# Radio.net
KiCad netlist of a schematic drawn in Altium Designer
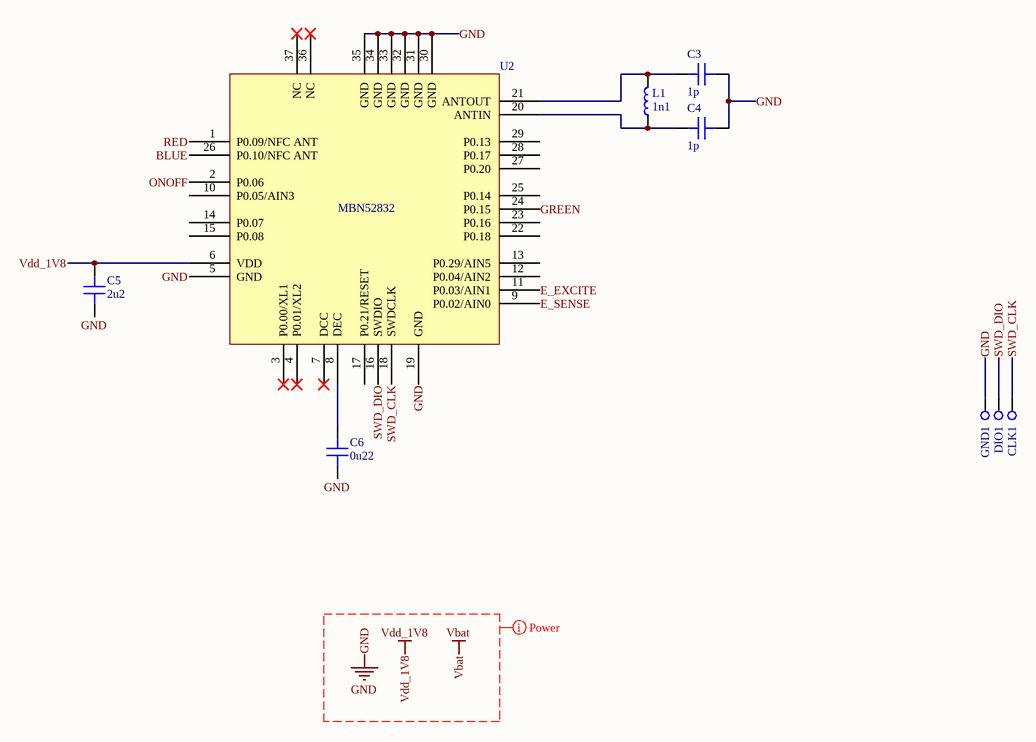
[diagram p0: Radio.SchDoc]

(export (version "E")
  (design (tool "Eeschema 10.0.6"))
  (components
    (comp (ref "C3")
      (value "1p")
      (footprint "CAP 0201/0603")
      (description "CAP CER 0201 1pF 50V ±0.1pF C0G")
      (fields (field (name "PART NUMBER") "GRM0335C1H1R0BA01D") (field (name "MANUFACTURER") "Murata"))
      (libsource (lib "ekuore-library") (part "Capacitor"))
    )
    (comp (ref "C4")
      (value "1p")
      (footprint "CAP 0201/0603")
      (description "CAP CER 0201 1pF 50V ±0.1pF C0G")
      (fields (field (name "PART NUMBER") "GRM0335C1H1R0BA01D") (field (name "MANUFACTURER") "Murata"))
      (libsource (lib "ekuore-library") (part "Capacitor"))
    )
    (comp (ref "C5")
      (value "2u2")
      (footprint "CAP 0402/1005")
      (description "CAP CER 0402 2.2uF 16V 10% X5R")
      (fields (field (name "PART NUMBER") "GRM155R61C225KE11D") (field (name "MANUFACTURER") "Murata"))
      (libsource (lib "ekuore-library") (part "Capacitor"))
    )
    (comp (ref "C6")
      (value "0u22")
      (footprint "CAP 0201/0603")
      (description "CAP CER 0201 0.22uF 10V 10% X5R")
      (fields (field (name "PART NUMBER") "GRM033R61A224KE90D") (field (name "MANUFACTURER") "Murata"))
      (libsource (lib "ekuore-library") (part "Capacitor"))
    )
    (comp (ref "CLK1")
      (value "Test Point")
      (footprint "TP SMD 1MM")
      (description "TP 1mm round pad")
      (fields (field (name "PART NUMBER") "TPSMD1"))
      (libsource (lib "ekuore-library") (part "Test Point"))
    )
    (comp (ref "DIO1")
      (value "Test Point")
      (footprint "TP SMD 1MM")
      (description "TP 1mm round pad")
      (fields (field (name "PART NUMBER") "TPSMD1"))
      (libsource (lib "ekuore-library") (part "Test Point"))
    )
    (comp (ref "GND1")
      (value "Test Point")
      (footprint "TP SMD 1MM")
      (description "TP 1mm round pad")
      (fields (field (name "PART NUMBER") "TPSMD1"))
      (libsource (lib "ekuore-library") (part "Test Point"))
    )
    (comp (ref "L1")
      (value "1n1")
      (footprint "FER 0402/1005")
      (description "IND 0201 1.1nH +-0.1nH 0.75A 0.1R")
      (fields (field (name "PART NUMBER") "LQP03TN1N1B02D_mod") (field (name "MANUFACTURER") "Murata"))
      (libsource (lib "ekuore-library") (part "Inductor"))
    )
    (comp (ref "U2")
      (value "MBN52832")
      (footprint "Murata MBN52832")
      (description "Bluetooth v5.0 (BLE) SMART SOC IoT/NFC 1Mbps 3.3V")
      (fields (field (name "PART NUMBER") "WSM-BL241-ADA-008") (field (name "MANUFACTURER") "Murata"))
      (libsource (lib "ekuore-library") (part "Murata MBN52832"))
    )
  )
  (nets
    (net (code "1") (name "/BLUE") (class "Default")
      (node (ref "U2") (pin "26") (pinfunction "P0.10/NFC_ANT_26") (pintype "passive"))
    )
    (net (code "2") (name "/E_EXCITE") (class "Default")
      (node (ref "U2") (pin "11") (pinfunction "P0.03/AIN1_11") (pintype "passive"))
    )
    (net (code "3") (name "/E_SENSE") (class "Default")
      (node (ref "U2") (pin "9") (pinfunction "P0.02/AIN0_9") (pintype "passive"))
    )
    (net (code "4") (name "/GREEN") (class "Default")
      (node (ref "U2") (pin "24") (pinfunction "P0.15_24") (pintype "passive"))
    )
    (net (code "5") (name "/ONOFF") (class "Default")
      (node (ref "U2") (pin "2") (pinfunction "P0.06_2") (pintype "passive"))
    )
    (net (code "6") (name "/RED") (class "Default")
      (node (ref "U2") (pin "1") (pinfunction "P0.09/NFC_ANT_1") (pintype "passive"))
    )
    (net (code "7") (name "/SWD_CLK") (class "Default")
      (node (ref "CLK1") (pin "1") (pinfunction "TP_1") (pintype "passive"))
      (node (ref "U2") (pin "18") (pinfunction "SWDCLK_18") (pintype "passive"))
    )
    (net (code "8") (name "/SWD_DIO") (class "Default")
      (node (ref "DIO1") (pin "1") (pinfunction "TP_1") (pintype "passive"))
      (node (ref "U2") (pin "16") (pinfunction "SWDIO_16") (pintype "passive"))
    )
    (net (code "9") (name "GND") (class "Default")
      (node (ref "C3") (pin "2") (pinfunction "2_2") (pintype "passive"))
      (node (ref "C4") (pin "2") (pinfunction "2_2") (pintype "passive"))
      (node (ref "C5") (pin "1") (pinfunction "1_1") (pintype "passive"))
      (node (ref "C6") (pin "1") (pinfunction "1_1") (pintype "passive"))
      (node (ref "GND1") (pin "1") (pinfunction "TP_1") (pintype "passive"))
      (node (ref "U2") (pin "19") (pinfunction "GND_19") (pintype "passive"))
      (node (ref "U2") (pin "30") (pinfunction "GND_30") (pintype "passive"))
      (node (ref "U2") (pin "31") (pinfunction "GND_31") (pintype "passive"))
      (node (ref "U2") (pin "32") (pinfunction "GND_32") (pintype "passive"))
      (node (ref "U2") (pin "33") (pinfunction "GND_33") (pintype "passive"))
      (node (ref "U2") (pin "34") (pinfunction "GND_34") (pintype "passive"))
      (node (ref "U2") (pin "35") (pinfunction "GND_35") (pintype "passive"))
      (node (ref "U2") (pin "5") (pinfunction "GND_5") (pintype "passive"))
    )
    (net (code "10") (name "Net-(U2-ANTIN)") (class "Default")
      (node (ref "C4") (pin "1") (pinfunction "1_1") (pintype "passive"))
      (node (ref "L1") (pin "1") (pinfunction "1_1") (pintype "passive"))
      (node (ref "U2") (pin "20") (pinfunction "ANTIN_20") (pintype "passive"))
    )
    (net (code "11") (name "Net-(U2-ANTOUT)") (class "Default")
      (node (ref "C3") (pin "1") (pinfunction "1_1") (pintype "passive"))
      (node (ref "L1") (pin "2") (pinfunction "2_2") (pintype "passive"))
      (node (ref "U2") (pin "21") (pinfunction "ANTOUT_21") (pintype "passive"))
    )
    (net (code "12") (name "Net-(U2-DEC)") (class "Default")
      (node (ref "C6") (pin "2") (pinfunction "2_2") (pintype "passive"))
      (node (ref "U2") (pin "8") (pinfunction "DEC_8") (pintype "passive"))
    )
    (net (code "14") (name "Vdd_1V8") (class "Default")
      (node (ref "C5") (pin "2") (pinfunction "2_2") (pintype "passive"))
      (node (ref "U2") (pin "6") (pinfunction "VDD_6") (pintype "passive"))
    )
    (net (code "15") (name "unconnected-(U2-DCC-Pad7)") (class "Default")
      (node (ref "U2") (pin "7") (pinfunction "DCC_7") (pintype "passive+no_connect"))
    )
    (net (code "16") (name "unconnected-(U2-NC-Pad36)") (class "Default")
      (node (ref "U2") (pin "36") (pinfunction "NC_36") (pintype "passive+no_connect"))
    )
    (net (code "17") (name "unconnected-(U2-NC-Pad37)") (class "Default")
      (node (ref "U2") (pin "37") (pinfunction "NC_37") (pintype "passive+no_connect"))
    )
    (net (code "18") (name "unconnected-(U2-P0.00{slash}XL1-Pad3)") (class "Default")
      (node (ref "U2") (pin "3") (pinfunction "P0.00/XL1_3") (pintype "passive+no_connect"))
    )
    (net (code "19") (name "unconnected-(U2-P0.01{slash}XL2-Pad4)") (class "Default")
      (node (ref "U2") (pin "4") (pinfunction "P0.01/XL2_4") (pintype "passive+no_connect"))
    )
    (net (code "20") (name "unconnected-(U2-P0.04{slash}AIN2-Pad12)") (class "Default")
      (node (ref "U2") (pin "12") (pinfunction "P0.04/AIN2_12") (pintype "passive"))
    )
    (net (code "21") (name "unconnected-(U2-P0.05{slash}AIN3-Pad10)") (class "Default")
      (node (ref "U2") (pin "10") (pinfunction "P0.05/AIN3_10") (pintype "passive"))
    )
    (net (code "22") (name "unconnected-(U2-P0.07-Pad14)") (class "Default")
      (node (ref "U2") (pin "14") (pinfunction "P0.07_14") (pintype "passive"))
    )
    (net (code "23") (name "unconnected-(U2-P0.08-Pad15)") (class "Default")
      (node (ref "U2") (pin "15") (pinfunction "P0.08_15") (pintype "passive"))
    )
    (net (code "24") (name "unconnected-(U2-P0.13-Pad29)") (class "Default")
      (node (ref "U2") (pin "29") (pinfunction "P0.13_29") (pintype "passive"))
    )
    (net (code "25") (name "unconnected-(U2-P0.14-Pad25)") (class "Default")
      (node (ref "U2") (pin "25") (pinfunction "P0.14_25") (pintype "passive"))
    )
    (net (code "26") (name "unconnected-(U2-P0.16-Pad23)") (class "Default")
      (node (ref "U2") (pin "23") (pinfunction "P0.16_23") (pintype "passive"))
    )
    (net (code "27") (name "unconnected-(U2-P0.17-Pad28)") (class "Default")
      (node (ref "U2") (pin "28") (pinfunction "P0.17_28") (pintype "passive"))
    )
    (net (code "28") (name "unconnected-(U2-P0.18-Pad22)") (class "Default")
      (node (ref "U2") (pin "22") (pinfunction "P0.18_22") (pintype "passive"))
    )
    (net (code "29") (name "unconnected-(U2-P0.20-Pad27)") (class "Default")
      (node (ref "U2") (pin "27") (pinfunction "P0.20_27") (pintype "passive"))
    )
    (net (code "30") (name "unconnected-(U2-P0.21{slash}RESET-Pad17)") (class "Default")
      (node (ref "U2") (pin "17") (pinfunction "P0.21/RESET_17") (pintype "passive"))
    )
    (net (code "31") (name "unconnected-(U2-P0.29{slash}AIN5-Pad13)") (class "Default")
      (node (ref "U2") (pin "13") (pinfunction "P0.29/AIN5_13") (pintype "passive"))
    )
  )
)
